# Final_Thesis.net
KiCad netlist of a schematic drawn in EAGLE
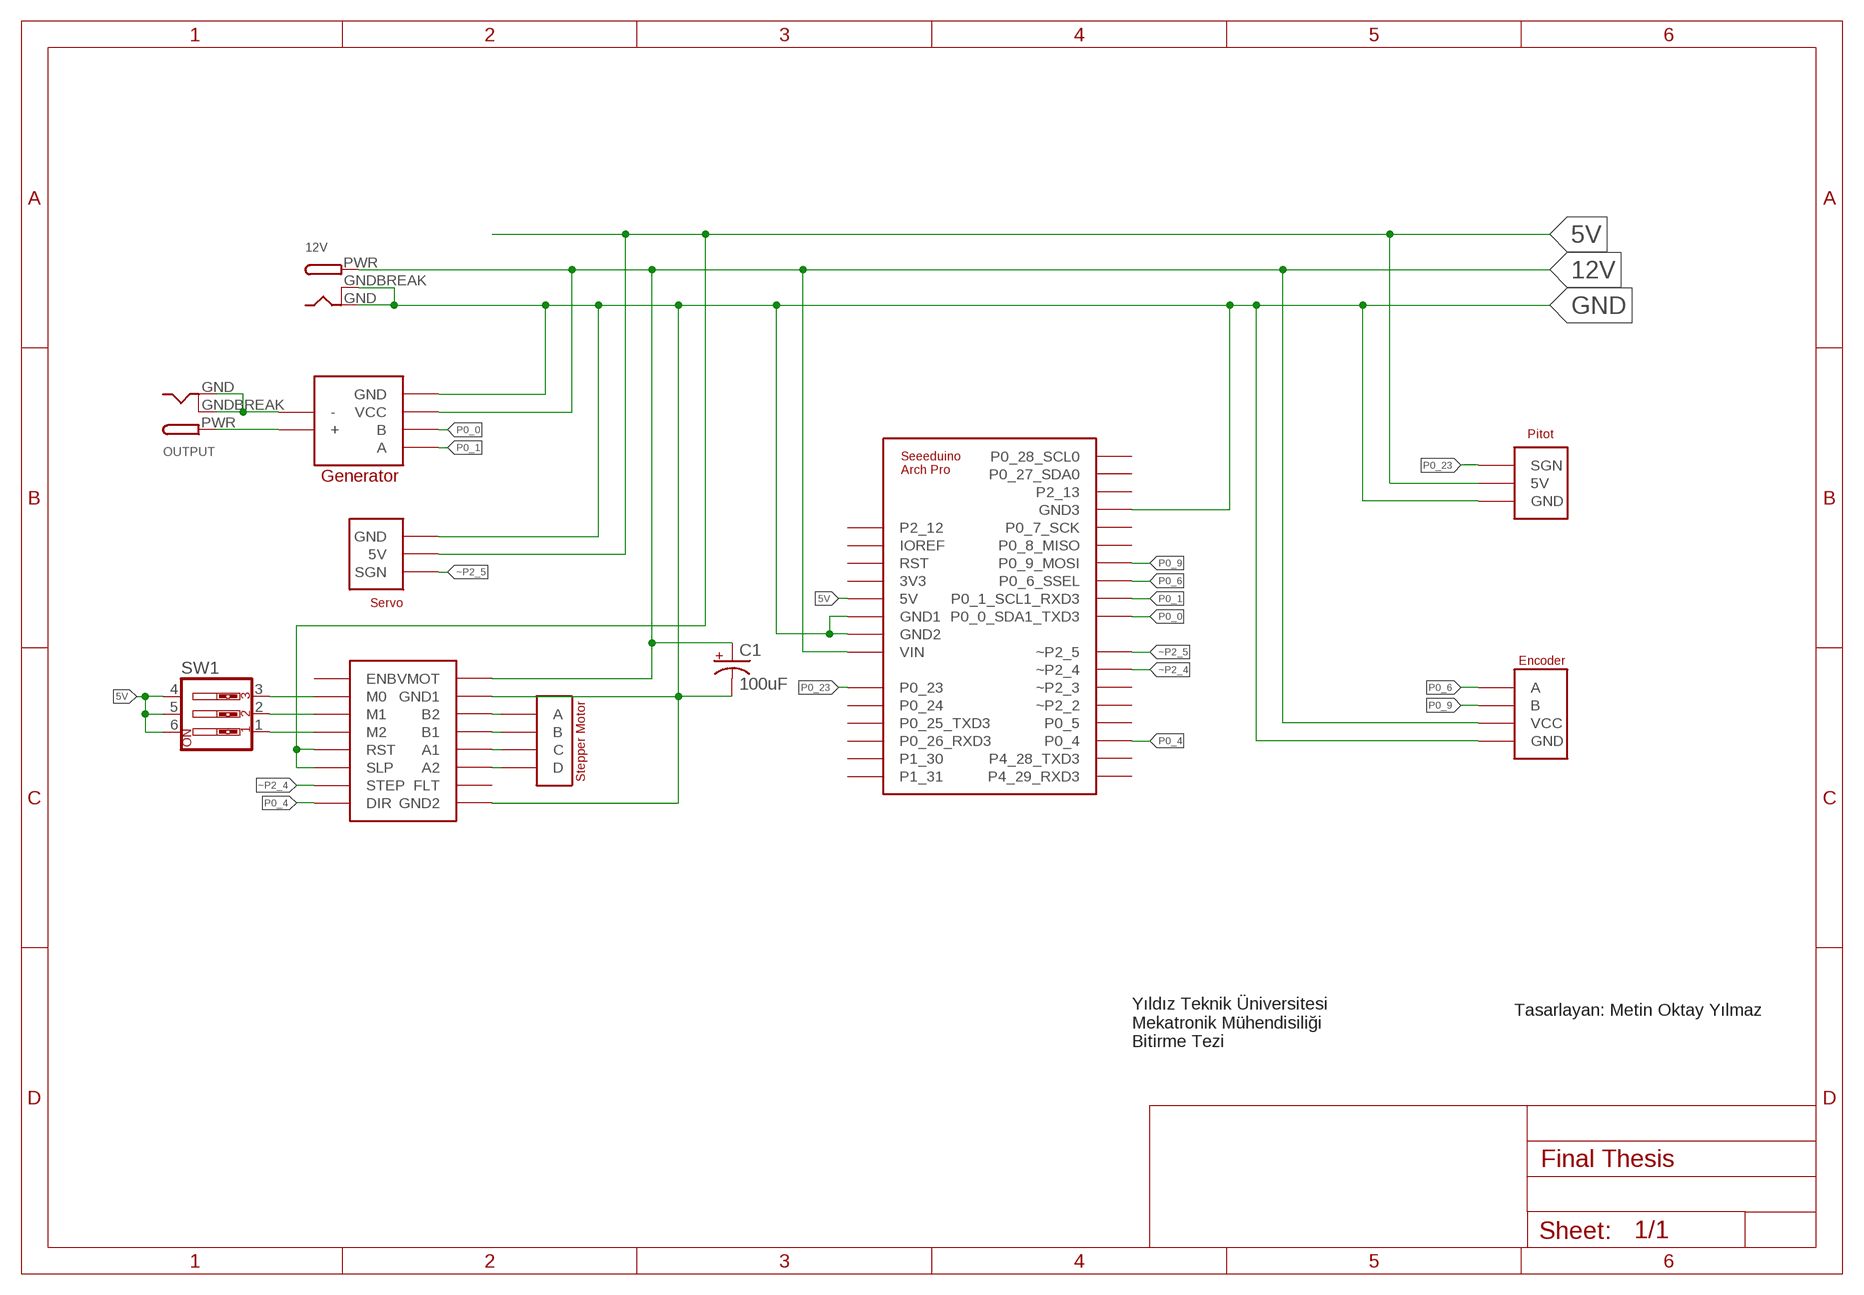
[diagram p0: schematic, sheet 1]

(export (version "E")
  (design (tool "Eeschema 10.0.6"))
  (components
    (comp (ref "12V")
      (value "DCBARRELPTH")
      (footprint "eagle-import:DCJACK_2MM_PTH")
      (libsource (lib "eagle-import") (part "DCBARRELPTH"))
    )
    (comp (ref "C1")
      (value "100uF")
      (footprint "eagle-import:CPOL-RADIAL-100UF-25V")
      (libsource (lib "eagle-import") (part "CAP_POLPTH1"))
    )
    (comp (ref "OUTPUT")
      (value "DCBARRELPTH")
      (footprint "eagle-import:DCJACK_2MM_PTH")
      (libsource (lib "eagle-import") (part "DCBARRELPTH"))
    )
    (comp (ref "SAP1")
      (value "ARCH_PROSHIELD")
      (footprint "eagle-import:ARCH_PRO")
      (libsource (lib "eagle-import") (part "ARCH_PROSHIELD"))
    )
    (comp (ref "SW1")
      (value "SW_DIP-3")
      (footprint "eagle-import:EDG-03")
      (libsource (lib "eagle-import") (part "SW_DIP-3"))
    )
    (comp (ref "U$1")
      (value "ENCODER")
      (footprint "eagle-import:ENCODER")
      (libsource (lib "eagle-import") (part "ENCODER"))
    )
    (comp (ref "U$2")
      (value "GENERATOR")
      (footprint "eagle-import:GENERATOR")
      (libsource (lib "eagle-import") (part "GENERATOR"))
    )
    (comp (ref "U$3")
      (value "PITOT")
      (footprint "eagle-import:PITOT")
      (libsource (lib "eagle-import") (part "PITOT"))
    )
    (comp (ref "U$4")
      (value "SERVO")
      (footprint "eagle-import:SERVO")
      (libsource (lib "eagle-import") (part "SERVO"))
    )
    (comp (ref "U$5")
      (value "STEPPER")
      (footprint "eagle-import:STEPPER")
      (libsource (lib "eagle-import") (part "STEPPER"))
    )
    (comp (ref "U$6")
      (value "STEPPER_DRIVER")
      (footprint "eagle-import:STEPPER_DRIVER")
      (libsource (lib "eagle-import") (part "STEPPER_DRIVER"))
    )
  )
  (nets
    (net (code "1") (name "/~{P2_4}") (class "Default")
      (node (ref "SAP1") (pin "~P2_4") (pinfunction "~{P2_4}_~P2_4") (pintype "bidirectional"))
      (node (ref "U$6") (pin "STEP") (pinfunction "STEP_STEP") (pintype "bidirectional"))
    )
    (net (code "2") (name "/~{P2_5}") (class "Default")
      (node (ref "SAP1") (pin "~P2_5") (pinfunction "~{P2_5}_~P2_5") (pintype "bidirectional"))
      (node (ref "U$4") (pin "SGN") (pinfunction "SGN_SGN") (pintype "bidirectional"))
    )
    (net (code "3") (name "5V") (class "Default")
      (node (ref "SAP1") (pin "5V") (pinfunction "5V_5V") (pintype "bidirectional"))
      (node (ref "SW1") (pin "4") (pinfunction "4_4") (pintype "passive"))
      (node (ref "SW1") (pin "5") (pinfunction "5_5") (pintype "passive"))
      (node (ref "SW1") (pin "6") (pinfunction "6_6") (pintype "passive"))
      (node (ref "U$3") (pin "5V") (pinfunction "5V_5V") (pintype "bidirectional"))
      (node (ref "U$4") (pin "5V") (pinfunction "5V_5V") (pintype "bidirectional"))
      (node (ref "U$6") (pin "RST") (pinfunction "RST_RST") (pintype "bidirectional"))
      (node (ref "U$6") (pin "SLP") (pinfunction "SLP_SLP") (pintype "bidirectional"))
    )
    (net (code "4") (name "12V") (class "Default")
      (node (ref "12V") (pin "PWR") (pinfunction "PWR_PWR") (pintype "power_in"))
      (node (ref "C1") (pin "1") (pinfunction "+_1") (pintype "passive"))
      (node (ref "SAP1") (pin "VIN") (pinfunction "VIN_VIN") (pintype "bidirectional"))
      (node (ref "U$1") (pin "VCC") (pinfunction "VCC_VCC") (pintype "bidirectional"))
      (node (ref "U$2") (pin "VCC") (pinfunction "VCC_VCC") (pintype "bidirectional"))
      (node (ref "U$6") (pin "VMOT") (pinfunction "VMOT_VMOT") (pintype "bidirectional"))
    )
    (net (code "5") (name "GND") (class "Default")
      (node (ref "12V") (pin "GND") (pinfunction "GND_GND") (pintype "power_in"))
      (node (ref "12V") (pin "GNDBREAK") (pinfunction "GNDBREAK_GNDBREAK") (pintype "power_in"))
      (node (ref "C1") (pin "2") (pinfunction "-_2") (pintype "passive"))
      (node (ref "SAP1") (pin "GND1") (pinfunction "GND1_GND1") (pintype "bidirectional"))
      (node (ref "SAP1") (pin "GND2") (pinfunction "GND2_GND2") (pintype "bidirectional"))
      (node (ref "SAP1") (pin "GND3") (pinfunction "GND3_GND3") (pintype "bidirectional"))
      (node (ref "U$1") (pin "GND") (pinfunction "GND_GND") (pintype "bidirectional"))
      (node (ref "U$2") (pin "GND") (pinfunction "GND_GND") (pintype "bidirectional"))
      (node (ref "U$3") (pin "GND") (pinfunction "GND_GND") (pintype "bidirectional"))
      (node (ref "U$4") (pin "GND") (pinfunction "GND_GND") (pintype "bidirectional"))
      (node (ref "U$6") (pin "GND") (pinfunction "GND1_GND") (pintype "bidirectional"))
      (node (ref "U$6") (pin "GND1") (pinfunction "GND2_GND1") (pintype "bidirectional"))
    )
    (net (code "6") (name "Net-(OUTPUT-PadGND)") (class "Default")
      (node (ref "OUTPUT") (pin "GND") (pinfunction "GND_GND") (pintype "power_in"))
      (node (ref "OUTPUT") (pin "GNDBREAK") (pinfunction "GNDBREAK_GNDBREAK") (pintype "power_in"))
      (node (ref "U$2") (pin "-") (pinfunction "-_-") (pintype "bidirectional"))
    )
    (net (code "7") (name "Net-(OUTPUT-PadPWR)") (class "Default")
      (node (ref "OUTPUT") (pin "PWR") (pinfunction "PWR_PWR") (pintype "power_in"))
      (node (ref "U$2") (pin "+") (pinfunction "+_+") (pintype "bidirectional"))
    )
    (net (code "8") (name "Net-(SW1-Pad1)") (class "Default")
      (node (ref "SW1") (pin "1") (pinfunction "1_1") (pintype "passive"))
      (node (ref "U$6") (pin "M2") (pinfunction "M2_M2") (pintype "bidirectional"))
    )
    (net (code "9") (name "Net-(SW1-Pad2)") (class "Default")
      (node (ref "SW1") (pin "2") (pinfunction "2_2") (pintype "passive"))
      (node (ref "U$6") (pin "M1") (pinfunction "M1_M1") (pintype "bidirectional"))
    )
    (net (code "10") (name "Net-(SW1-Pad3)") (class "Default")
      (node (ref "SW1") (pin "3") (pinfunction "3_3") (pintype "passive"))
      (node (ref "U$6") (pin "M0") (pinfunction "M0_M0") (pintype "bidirectional"))
    )
    (net (code "11") (name "Net-(U$5-PadA)") (class "Default")
      (node (ref "U$5") (pin "A") (pinfunction "A_A") (pintype "bidirectional"))
      (node (ref "U$6") (pin "B2") (pinfunction "B2_B2") (pintype "bidirectional"))
    )
    (net (code "12") (name "Net-(U$5-PadB)") (class "Default")
      (node (ref "U$5") (pin "B") (pinfunction "B_B") (pintype "bidirectional"))
      (node (ref "U$6") (pin "B1") (pinfunction "B1_B1") (pintype "bidirectional"))
    )
    (net (code "13") (name "Net-(U$5-PadC)") (class "Default")
      (node (ref "U$5") (pin "C") (pinfunction "C_C") (pintype "bidirectional"))
      (node (ref "U$6") (pin "A1") (pinfunction "A1_A1") (pintype "bidirectional"))
    )
    (net (code "14") (name "Net-(U$5-PadD)") (class "Default")
      (node (ref "U$5") (pin "D") (pinfunction "D_D") (pintype "bidirectional"))
      (node (ref "U$6") (pin "A2") (pinfunction "A2_A2") (pintype "bidirectional"))
    )
    (net (code "15") (name "P0_0") (class "Default")
      (node (ref "SAP1") (pin "P0_0_SDA1_TXD3") (pinfunction "P0_0_SDA1_TXD3_P0_0_SDA1_TXD3") (pintype "bidirectional"))
      (node (ref "U$2") (pin "B") (pinfunction "B_B") (pintype "bidirectional"))
    )
    (net (code "16") (name "P0_1") (class "Default")
      (node (ref "SAP1") (pin "P0_1_SCL1_RXD3") (pinfunction "P0_1_SCL1_RXD3_P0_1_SCL1_RXD3") (pintype "bidirectional"))
      (node (ref "U$2") (pin "A") (pinfunction "A_A") (pintype "bidirectional"))
    )
    (net (code "17") (name "P0_4") (class "Default")
      (node (ref "SAP1") (pin "P0_4") (pinfunction "P0_4_P0_4") (pintype "bidirectional"))
      (node (ref "U$6") (pin "DIR") (pinfunction "DIR_DIR") (pintype "bidirectional"))
    )
    (net (code "18") (name "P0_6") (class "Default")
      (node (ref "SAP1") (pin "P0_6_SSEL") (pinfunction "P0_6_SSEL_P0_6_SSEL") (pintype "bidirectional"))
      (node (ref "U$1") (pin "A") (pinfunction "A_A") (pintype "bidirectional"))
    )
    (net (code "19") (name "P0_9") (class "Default")
      (node (ref "SAP1") (pin "P0_9_MOSI") (pinfunction "P0_9_MOSI_P0_9_MOSI") (pintype "bidirectional"))
      (node (ref "U$1") (pin "B") (pinfunction "B_B") (pintype "bidirectional"))
    )
    (net (code "20") (name "P0_23") (class "Default")
      (node (ref "SAP1") (pin "P0_23") (pinfunction "P0_23_P0_23") (pintype "bidirectional"))
      (node (ref "U$3") (pin "SGN") (pinfunction "SGN_SGN") (pintype "bidirectional"))
    )
    (net (code "21") (name "unconnected-(SAP1-Pad3V3)") (class "Default")
      (node (ref "SAP1") (pin "3V3") (pinfunction "3V3_3V3") (pintype "bidirectional"))
    )
    (net (code "22") (name "unconnected-(SAP1-PadIOREF)") (class "Default")
      (node (ref "SAP1") (pin "IOREF") (pinfunction "IOREF_IOREF") (pintype "bidirectional"))
    )
    (net (code "23") (name "unconnected-(SAP1-PadP0_5)") (class "Default")
      (node (ref "SAP1") (pin "P0_5") (pinfunction "P0_5_P0_5") (pintype "bidirectional"))
    )
    (net (code "24") (name "unconnected-(SAP1-PadP0_7_SCK)") (class "Default")
      (node (ref "SAP1") (pin "P0_7_SCK") (pinfunction "P0_7_SCK_P0_7_SCK") (pintype "bidirectional"))
    )
    (net (code "25") (name "unconnected-(SAP1-PadP0_8_MISO)") (class "Default")
      (node (ref "SAP1") (pin "P0_8_MISO") (pinfunction "P0_8_MISO_P0_8_MISO") (pintype "bidirectional"))
    )
    (net (code "26") (name "unconnected-(SAP1-PadP0_24)") (class "Default")
      (node (ref "SAP1") (pin "P0_24") (pinfunction "P0_24_P0_24") (pintype "bidirectional"))
    )
    (net (code "27") (name "unconnected-(SAP1-PadP0_25_TXD3)") (class "Default")
      (node (ref "SAP1") (pin "P0_25_TXD3") (pinfunction "P0_25_TXD3_P0_25_TXD3") (pintype "bidirectional"))
    )
    (net (code "28") (name "unconnected-(SAP1-PadP0_26_RXD3)") (class "Default")
      (node (ref "SAP1") (pin "P0_26_RXD3") (pinfunction "P0_26_RXD3_P0_26_RXD3") (pintype "bidirectional"))
    )
    (net (code "29") (name "unconnected-(SAP1-PadP0_27_SDA0)") (class "Default")
      (node (ref "SAP1") (pin "P0_27_SDA0") (pinfunction "P0_27_SDA0_P0_27_SDA0") (pintype "bidirectional"))
    )
    (net (code "30") (name "unconnected-(SAP1-PadP0_28_SCL0)") (class "Default")
      (node (ref "SAP1") (pin "P0_28_SCL0") (pinfunction "P0_28_SCL0_P0_28_SCL0") (pintype "bidirectional"))
    )
    (net (code "31") (name "unconnected-(SAP1-PadP1_30)") (class "Default")
      (node (ref "SAP1") (pin "P1_30") (pinfunction "P1_30_P1_30") (pintype "bidirectional"))
    )
    (net (code "32") (name "unconnected-(SAP1-PadP1_31)") (class "Default")
      (node (ref "SAP1") (pin "P1_31") (pinfunction "P1_31_P1_31") (pintype "bidirectional"))
    )
    (net (code "33") (name "unconnected-(SAP1-PadP2_12)") (class "Default")
      (node (ref "SAP1") (pin "P2_12") (pinfunction "P2_12_P2_12") (pintype "bidirectional"))
    )
    (net (code "34") (name "unconnected-(SAP1-PadP2_13)") (class "Default")
      (node (ref "SAP1") (pin "P2_13") (pinfunction "P2_13_P2_13") (pintype "bidirectional"))
    )
    (net (code "35") (name "unconnected-(SAP1-PadP4_28_TXD3)") (class "Default")
      (node (ref "SAP1") (pin "P4_28_TXD3") (pinfunction "P4_28_TXD3_P4_28_TXD3") (pintype "bidirectional"))
    )
    (net (code "36") (name "unconnected-(SAP1-PadP4_29_RXD3)") (class "Default")
      (node (ref "SAP1") (pin "P4_29_RXD3") (pinfunction "P4_29_RXD3_P4_29_RXD3") (pintype "bidirectional"))
    )
    (net (code "37") (name "unconnected-(SAP1-PadRST)") (class "Default")
      (node (ref "SAP1") (pin "RST") (pinfunction "RST_RST") (pintype "bidirectional"))
    )
    (net (code "38") (name "unconnected-(SAP1-~{P2_2}-Pad~P2_2)") (class "Default")
      (node (ref "SAP1") (pin "~P2_2") (pinfunction "~{P2_2}_~P2_2") (pintype "bidirectional"))
    )
    (net (code "39") (name "unconnected-(SAP1-~{P2_3}-Pad~P2_3)") (class "Default")
      (node (ref "SAP1") (pin "~P2_3") (pinfunction "~{P2_3}_~P2_3") (pintype "bidirectional"))
    )
    (net (code "40") (name "unconnected-(U$6-PadENB)") (class "Default")
      (node (ref "U$6") (pin "ENB") (pinfunction "ENB_ENB") (pintype "bidirectional"))
    )
    (net (code "41") (name "unconnected-(U$6-PadFLT)") (class "Default")
      (node (ref "U$6") (pin "FLT") (pinfunction "FLT_FLT") (pintype "bidirectional"))
    )
  )
)
